# temp.net
KiCad netlist of a schematic drawn in EAGLE
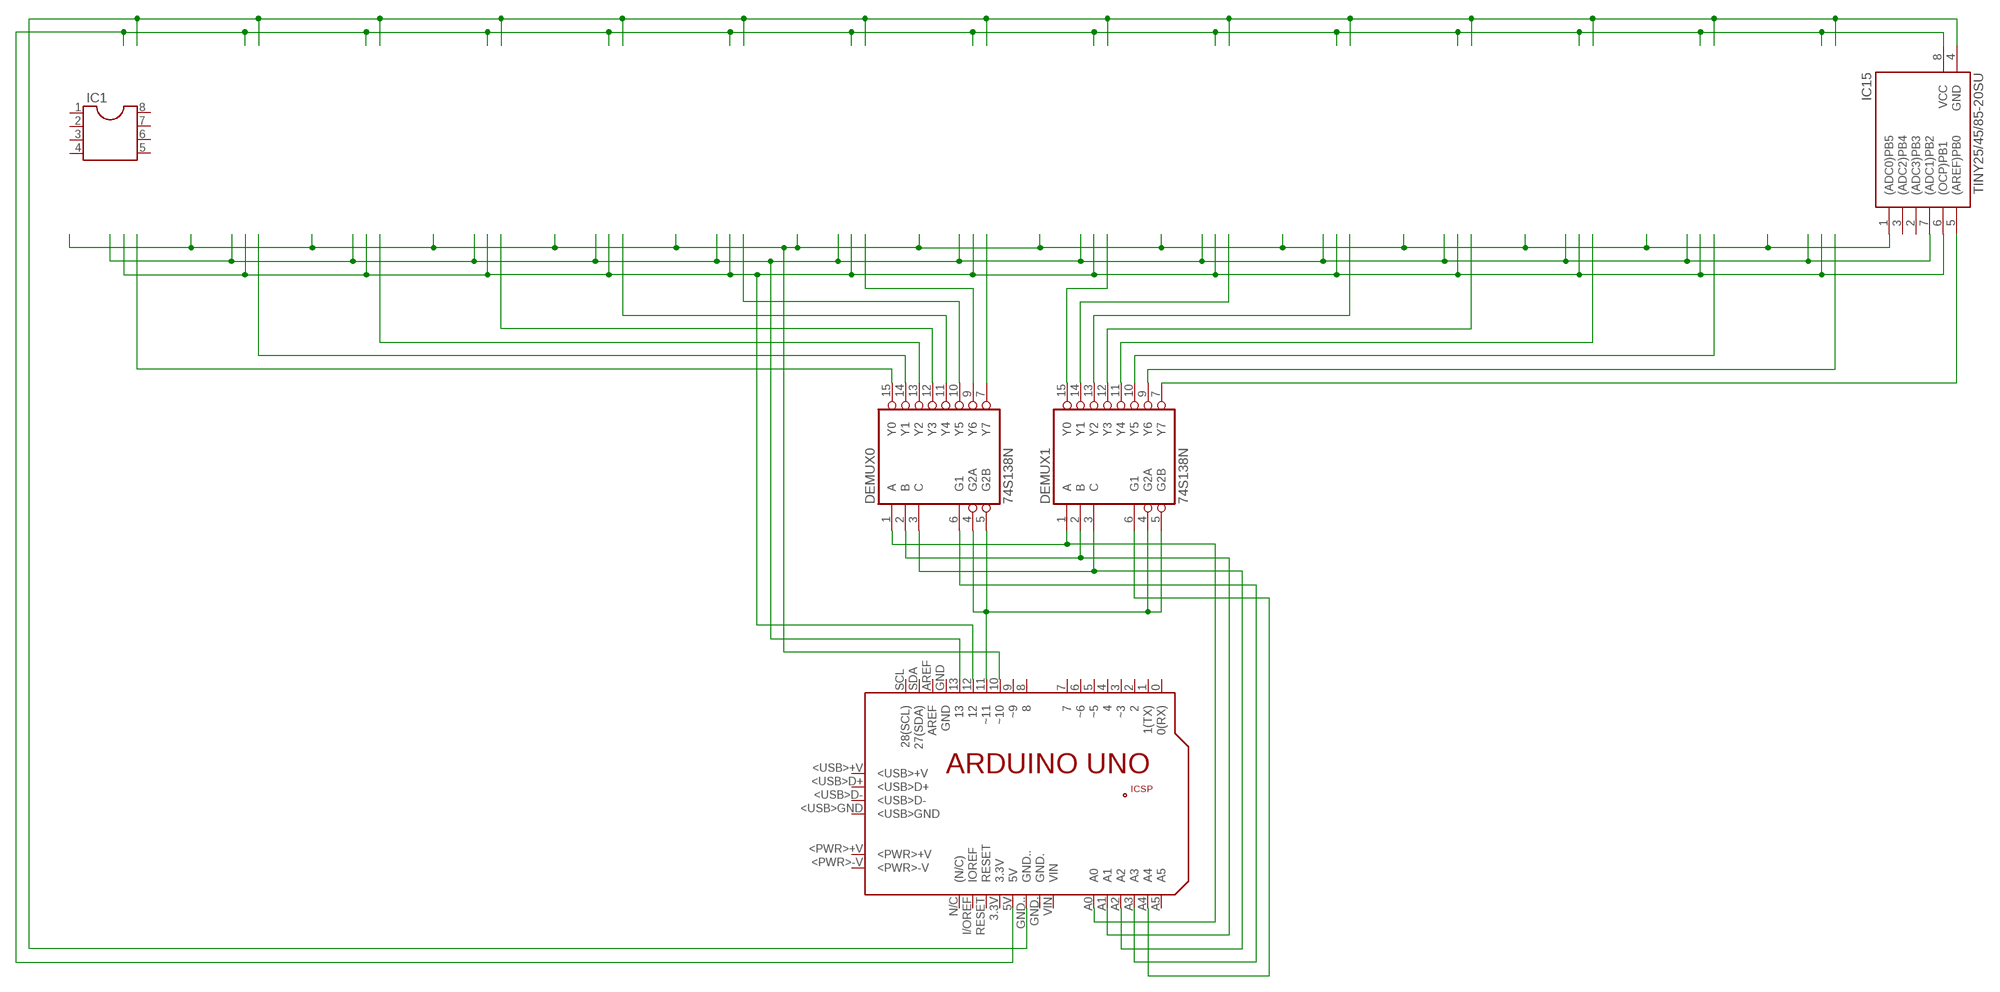
[diagram p0: schematic, sheet 1]

(export (version "E")
  (design (tool "Eeschema 10.0.6"))
  (components
    (comp (ref "DEMUX0")
      (value "74S138N")
      (footprint "eagle-import:DIL16")
      (libsource (lib "eagle-import") (part "74138NS"))
    )
    (comp (ref "DEMUX1")
      (value "74S138N")
      (footprint "eagle-import:DIL16")
      (libsource (lib "eagle-import") (part "74138NS"))
    )
    (comp (ref "IC1")
      (value "DIL8")
      (footprint "eagle-import:DIL08")
      (libsource (lib "eagle-import") (part "DIL8"))
    )
    (comp (ref "IC15")
      (value "TINY25/45/85-20SU")
      (footprint "eagle-import:SOIC8")
      (libsource (lib "eagle-import") (part "TINY25/45/85-20SU"))
    )
    (comp (ref "PCB1")
      (value "ARDUINO_UNO")
      (footprint "eagle-import:ARDUINO_UNO")
      (libsource (lib "eagle-import") (part "ARDUINO_UNO"))
    )
  )
  (nets
    (net (code "1") (name "Net-(DEMUX0A-A)") (class "Default")
      (node (ref "DEMUX0") (pin "1") (pinfunction "A_1") (pintype "input"))
      (node (ref "DEMUX1") (pin "1") (pinfunction "A_1") (pintype "input"))
      (node (ref "PCB1") (pin "A0") (pinfunction "A0_A0") (pintype "bidirectional"))
    )
    (net (code "2") (name "Net-(DEMUX0A-B)") (class "Default")
      (node (ref "DEMUX0") (pin "2") (pinfunction "B_2") (pintype "input"))
      (node (ref "DEMUX1") (pin "2") (pinfunction "B_2") (pintype "input"))
      (node (ref "PCB1") (pin "A1") (pinfunction "A1_A1") (pintype "bidirectional"))
    )
    (net (code "3") (name "Net-(DEMUX0A-C)") (class "Default")
      (node (ref "DEMUX0") (pin "3") (pinfunction "C_3") (pintype "input"))
      (node (ref "DEMUX1") (pin "3") (pinfunction "C_3") (pintype "input"))
      (node (ref "PCB1") (pin "A2") (pinfunction "A2_A2") (pintype "bidirectional"))
    )
    (net (code "4") (name "Net-(DEMUX0A-G1)") (class "Default")
      (node (ref "DEMUX0") (pin "6") (pinfunction "G1_6") (pintype "input"))
      (node (ref "PCB1") (pin "A3") (pinfunction "A3_A3") (pintype "bidirectional"))
    )
    (net (code "5") (name "Net-(DEMUX0A-G2A)") (class "Default")
      (node (ref "DEMUX0") (pin "4") (pinfunction "G2A_4") (pintype "input"))
      (node (ref "DEMUX0") (pin "5") (pinfunction "G2B_5") (pintype "input"))
      (node (ref "DEMUX1") (pin "4") (pinfunction "G2A_4") (pintype "input"))
      (node (ref "DEMUX1") (pin "5") (pinfunction "G2B_5") (pintype "input"))
      (node (ref "PCB1") (pin "11") (pinfunction "~{11}_11") (pintype "bidirectional"))
    )
    (net (code "6") (name "Net-(DEMUX1A-G1)") (class "Default")
      (node (ref "DEMUX1") (pin "6") (pinfunction "G1_6") (pintype "input"))
      (node (ref "PCB1") (pin "A4") (pinfunction "A4_A4") (pintype "bidirectional"))
    )
    (net (code "7") (name "Net-(DEMUX1A-Y7)") (class "Default")
      (node (ref "DEMUX1") (pin "7") (pinfunction "Y7_7") (pintype "output"))
      (node (ref "IC15") (pin "5") (pinfunction "(AREF)PB0_5") (pintype "bidirectional"))
    )
    (net (code "8") (name "Net-(IC15-(ADC0)PB5)") (class "Default")
      (node (ref "IC15") (pin "1") (pinfunction "(ADC0)PB5_1") (pintype "bidirectional"))
      (node (ref "PCB1") (pin "10") (pinfunction "~{10}_10") (pintype "bidirectional"))
    )
    (net (code "9") (name "Net-(IC15-(ADC1)PB2)") (class "Default")
      (node (ref "IC15") (pin "7") (pinfunction "(ADC1)PB2_7") (pintype "bidirectional"))
      (node (ref "PCB1") (pin "13") (pinfunction "13_13") (pintype "bidirectional"))
    )
    (net (code "10") (name "Net-(IC15-(OCP)PB1)") (class "Default")
      (node (ref "IC15") (pin "6") (pinfunction "(OCP)PB1_6") (pintype "bidirectional"))
      (node (ref "PCB1") (pin "12") (pinfunction "12_12") (pintype "bidirectional"))
    )
    (net (code "11") (name "Net-(IC15-GND)") (class "Default")
      (node (ref "IC15") (pin "4") (pinfunction "GND_4") (pintype "power_in"))
      (node (ref "PCB1") (pin "GND..") (pinfunction "GND.._GND..") (pintype "bidirectional"))
    )
    (net (code "12") (name "Net-(IC15-VCC)") (class "Default")
      (node (ref "IC15") (pin "8") (pinfunction "VCC_8") (pintype "power_in"))
      (node (ref "PCB1") (pin "5V") (pinfunction "5V_5V") (pintype "bidirectional"))
    )
    (net (code "13") (name "unconnected-(DEMUX0A-Y0-Pad15)") (class "Default")
      (node (ref "DEMUX0") (pin "15") (pinfunction "Y0_15") (pintype "output"))
    )
    (net (code "14") (name "unconnected-(DEMUX0A-Y1-Pad14)") (class "Default")
      (node (ref "DEMUX0") (pin "14") (pinfunction "Y1_14") (pintype "output"))
    )
    (net (code "15") (name "unconnected-(DEMUX0A-Y2-Pad13)") (class "Default")
      (node (ref "DEMUX0") (pin "13") (pinfunction "Y2_13") (pintype "output"))
    )
    (net (code "16") (name "unconnected-(DEMUX0A-Y3-Pad12)") (class "Default")
      (node (ref "DEMUX0") (pin "12") (pinfunction "Y3_12") (pintype "output"))
    )
    (net (code "17") (name "unconnected-(DEMUX0A-Y4-Pad11)") (class "Default")
      (node (ref "DEMUX0") (pin "11") (pinfunction "Y4_11") (pintype "output"))
    )
    (net (code "18") (name "unconnected-(DEMUX0A-Y5-Pad10)") (class "Default")
      (node (ref "DEMUX0") (pin "10") (pinfunction "Y5_10") (pintype "output"))
    )
    (net (code "19") (name "unconnected-(DEMUX0A-Y6-Pad9)") (class "Default")
      (node (ref "DEMUX0") (pin "9") (pinfunction "Y6_9") (pintype "output"))
    )
    (net (code "20") (name "unconnected-(DEMUX0A-Y7-Pad7)") (class "Default")
      (node (ref "DEMUX0") (pin "7") (pinfunction "Y7_7") (pintype "output"))
    )
    (net (code "21") (name "unconnected-(DEMUX1A-Y0-Pad15)") (class "Default")
      (node (ref "DEMUX1") (pin "15") (pinfunction "Y0_15") (pintype "output"))
    )
    (net (code "22") (name "unconnected-(DEMUX1A-Y1-Pad14)") (class "Default")
      (node (ref "DEMUX1") (pin "14") (pinfunction "Y1_14") (pintype "output"))
    )
    (net (code "23") (name "unconnected-(DEMUX1A-Y2-Pad13)") (class "Default")
      (node (ref "DEMUX1") (pin "13") (pinfunction "Y2_13") (pintype "output"))
    )
    (net (code "24") (name "unconnected-(DEMUX1A-Y3-Pad12)") (class "Default")
      (node (ref "DEMUX1") (pin "12") (pinfunction "Y3_12") (pintype "output"))
    )
    (net (code "25") (name "unconnected-(DEMUX1A-Y4-Pad11)") (class "Default")
      (node (ref "DEMUX1") (pin "11") (pinfunction "Y4_11") (pintype "output"))
    )
    (net (code "26") (name "unconnected-(DEMUX1A-Y5-Pad10)") (class "Default")
      (node (ref "DEMUX1") (pin "10") (pinfunction "Y5_10") (pintype "output"))
    )
    (net (code "27") (name "unconnected-(DEMUX1A-Y6-Pad9)") (class "Default")
      (node (ref "DEMUX1") (pin "9") (pinfunction "Y6_9") (pintype "output"))
    )
    (net (code "28") (name "unconnected-(IC1-Pad1)") (class "Default")
      (node (ref "IC1") (pin "1") (pinfunction "1_1") (pintype "passive"))
    )
    (net (code "29") (name "unconnected-(IC1-Pad2)") (class "Default")
      (node (ref "IC1") (pin "2") (pinfunction "2_2") (pintype "passive"))
    )
    (net (code "30") (name "unconnected-(IC1-Pad3)") (class "Default")
      (node (ref "IC1") (pin "3") (pinfunction "3_3") (pintype "passive"))
    )
    (net (code "31") (name "unconnected-(IC1-Pad4)") (class "Default")
      (node (ref "IC1") (pin "4") (pinfunction "4_4") (pintype "passive"))
    )
    (net (code "32") (name "unconnected-(IC1-Pad5)") (class "Default")
      (node (ref "IC1") (pin "5") (pinfunction "5_5") (pintype "passive"))
    )
    (net (code "33") (name "unconnected-(IC1-Pad6)") (class "Default")
      (node (ref "IC1") (pin "6") (pinfunction "6_6") (pintype "passive"))
    )
    (net (code "34") (name "unconnected-(IC1-Pad7)") (class "Default")
      (node (ref "IC1") (pin "7") (pinfunction "7_7") (pintype "passive"))
    )
    (net (code "35") (name "unconnected-(IC1-Pad8)") (class "Default")
      (node (ref "IC1") (pin "8") (pinfunction "8_8") (pintype "passive"))
    )
    (net (code "36") (name "unconnected-(IC15-(ADC2)PB4-Pad3)") (class "Default")
      (node (ref "IC15") (pin "3") (pinfunction "(ADC2)PB4_3") (pintype "bidirectional"))
    )
    (net (code "37") (name "unconnected-(IC15-(ADC3)PB3-Pad2)") (class "Default")
      (node (ref "IC15") (pin "2") (pinfunction "(ADC3)PB3_2") (pintype "bidirectional"))
    )
    (net (code "38") (name "unconnected-(PCB1-(N{slash}C)-PadN{slash}C)") (class "Default")
      (node (ref "PCB1") (pin "N/C") (pinfunction "(N/C)_N/C") (pintype "bidirectional"))
    )
    (net (code "39") (name "unconnected-(PCB1-0(RX)-Pad0)") (class "Default")
      (node (ref "PCB1") (pin "0") (pinfunction "0(RX)_0") (pintype "bidirectional"))
    )
    (net (code "40") (name "unconnected-(PCB1-1(TX)-Pad1)") (class "Default")
      (node (ref "PCB1") (pin "1") (pinfunction "1(TX)_1") (pintype "bidirectional"))
    )
    (net (code "41") (name "unconnected-(PCB1-27(SDA)-PadSDA)") (class "Default")
      (node (ref "PCB1") (pin "SDA") (pinfunction "27(SDA)_SDA") (pintype "bidirectional"))
    )
    (net (code "42") (name "unconnected-(PCB1-28(SCL)-PadSCL)") (class "Default")
      (node (ref "PCB1") (pin "SCL") (pinfunction "28(SCL)_SCL") (pintype "bidirectional"))
    )
    (net (code "43") (name "unconnected-(PCB1-IOREF-PadI{slash}OREF)") (class "Default")
      (node (ref "PCB1") (pin "I/OREF") (pinfunction "IOREF_I/OREF") (pintype "bidirectional"))
    )
    (net (code "44") (name "unconnected-(PCB1-Pad+5V)") (class "Default")
      (node (ref "PCB1") (pin "+5V") (pinfunction "+5V_+5V") (pintype "bidirectional"))
    )
    (net (code "45") (name "unconnected-(PCB1-Pad2)") (class "Default")
      (node (ref "PCB1") (pin "2") (pinfunction "2_2") (pintype "bidirectional"))
    )
    (net (code "46") (name "unconnected-(PCB1-Pad3.3V)") (class "Default")
      (node (ref "PCB1") (pin "3.3V") (pinfunction "3.3V_3.3V") (pintype "bidirectional"))
    )
    (net (code "47") (name "unconnected-(PCB1-Pad4)") (class "Default")
      (node (ref "PCB1") (pin "4") (pinfunction "4_4") (pintype "bidirectional"))
    )
    (net (code "48") (name "unconnected-(PCB1-Pad7)") (class "Default")
      (node (ref "PCB1") (pin "7") (pinfunction "7_7") (pintype "bidirectional"))
    )
    (net (code "49") (name "unconnected-(PCB1-Pad8)") (class "Default")
      (node (ref "PCB1") (pin "8") (pinfunction "8_8") (pintype "bidirectional"))
    )
    (net (code "50") (name "unconnected-(PCB1-Pad<PWR>+V)") (class "Default")
      (node (ref "PCB1") (pin "<PWR>+V") (pinfunction "<PWR>+V_<PWR>+V") (pintype "bidirectional"))
    )
    (net (code "51") (name "unconnected-(PCB1-Pad<PWR>-V)") (class "Default")
      (node (ref "PCB1") (pin "<PWR>-V") (pinfunction "<PWR>-V_<PWR>-V") (pintype "bidirectional"))
    )
    (net (code "52") (name "unconnected-(PCB1-Pad<USB>+V)") (class "Default")
      (node (ref "PCB1") (pin "<USB>+V") (pinfunction "<USB>+V_<USB>+V") (pintype "bidirectional"))
    )
    (net (code "53") (name "unconnected-(PCB1-Pad<USB>D+)") (class "Default")
      (node (ref "PCB1") (pin "<USB>D+") (pinfunction "<USB>D+_<USB>D+") (pintype "bidirectional"))
    )
    (net (code "54") (name "unconnected-(PCB1-Pad<USB>D-)") (class "Default")
      (node (ref "PCB1") (pin "<USB>D-") (pinfunction "<USB>D-_<USB>D-") (pintype "bidirectional"))
    )
    (net (code "55") (name "unconnected-(PCB1-Pad<USB>GND)") (class "Default")
      (node (ref "PCB1") (pin "<USB>GND") (pinfunction "<USB>GND_<USB>GND") (pintype "bidirectional"))
    )
    (net (code "56") (name "unconnected-(PCB1-PadA5)") (class "Default")
      (node (ref "PCB1") (pin "A5") (pinfunction "A5_A5") (pintype "bidirectional"))
    )
    (net (code "57") (name "unconnected-(PCB1-PadAREF)") (class "Default")
      (node (ref "PCB1") (pin "AREF") (pinfunction "AREF_AREF") (pintype "bidirectional"))
    )
    (net (code "58") (name "unconnected-(PCB1-PadGND)") (class "Default")
      (node (ref "PCB1") (pin "GND") (pinfunction "GND_GND") (pintype "bidirectional"))
    )
    (net (code "59") (name "unconnected-(PCB1-PadGND.)") (class "Default")
      (node (ref "PCB1") (pin "GND.") (pinfunction "GND._GND.") (pintype "bidirectional"))
    )
    (net (code "60") (name "unconnected-(PCB1-PadGND_)") (class "Default")
      (node (ref "PCB1") (pin "GND_") (pinfunction "GND__GND_") (pintype "bidirectional"))
    )
    (net (code "61") (name "unconnected-(PCB1-PadMISO)") (class "Default")
      (node (ref "PCB1") (pin "MISO") (pinfunction "MISO_MISO") (pintype "bidirectional"))
    )
    (net (code "62") (name "unconnected-(PCB1-PadMOSI)") (class "Default")
      (node (ref "PCB1") (pin "MOSI") (pinfunction "MOSI_MOSI") (pintype "bidirectional"))
    )
    (net (code "63") (name "unconnected-(PCB1-PadRESET)") (class "Default")
      (node (ref "PCB1") (pin "RESET") (pinfunction "RESET_RESET") (pintype "bidirectional"))
    )
    (net (code "64") (name "unconnected-(PCB1-PadRESET.)") (class "Default")
      (node (ref "PCB1") (pin "RESET.") (pinfunction "RESET._RESET.") (pintype "bidirectional"))
    )
    (net (code "65") (name "unconnected-(PCB1-PadSCK)") (class "Default")
      (node (ref "PCB1") (pin "SCK") (pinfunction "SCK_SCK") (pintype "bidirectional"))
    )
    (net (code "66") (name "unconnected-(PCB1-PadVIN)") (class "Default")
      (node (ref "PCB1") (pin "VIN") (pinfunction "VIN_VIN") (pintype "bidirectional"))
    )
    (net (code "67") (name "unconnected-(PCB1-~{3}-Pad3)") (class "Default")
      (node (ref "PCB1") (pin "3") (pinfunction "~{3}_3") (pintype "bidirectional"))
    )
    (net (code "68") (name "unconnected-(PCB1-~{5}-Pad5)") (class "Default")
      (node (ref "PCB1") (pin "5") (pinfunction "~{5}_5") (pintype "bidirectional"))
    )
    (net (code "69") (name "unconnected-(PCB1-~{6}-Pad6)") (class "Default")
      (node (ref "PCB1") (pin "6") (pinfunction "~{6}_6") (pintype "bidirectional"))
    )
    (net (code "70") (name "unconnected-(PCB1-~{9}-Pad9)") (class "Default")
      (node (ref "PCB1") (pin "9") (pinfunction "~{9}_9") (pintype "bidirectional"))
    )
  )
)
